# buck.net
KiCad netlist of a schematic drawn in Altium Designer
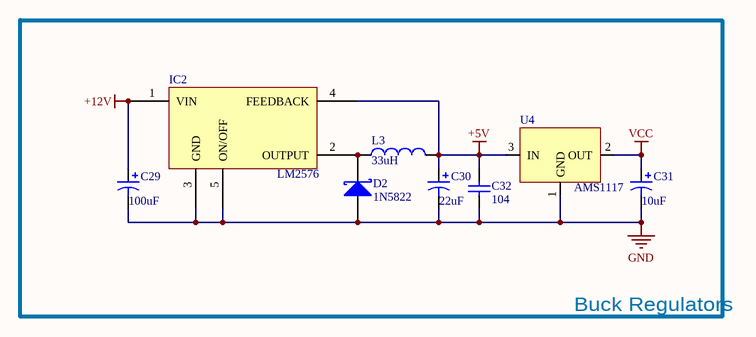
[diagram p0: buck.SchDoc]

(export (version "E")
  (design (tool "Eeschema 10.0.6"))
  (components
    (comp (ref "C29")
      (value "100uF")
      (footprint "CM E(8*10.2)")
      (description "Polarized Capacitor (Radial)")
      (fields (field (name "PUBLISHER") "Altium Limited"))
      (libsource (lib "Miscellaneous Devices") (part "Cap Pol1"))
    )
    (comp (ref "C30")
      (value "22uF")
      (footprint "CD A(3216)")
      (description "Polarized Capacitor (Radial)")
      (fields (field (name "PUBLISHER") "Altium Limited"))
      (libsource (lib "Miscellaneous Devices") (part "Cap Pol1"))
    )
    (comp (ref "C31")
      (value "10uF")
      (footprint "CD A(3216)")
      (description "Polarized Capacitor (Radial)")
      (fields (field (name "PUBLISHER") "Altium Limited"))
      (libsource (lib "Miscellaneous Devices") (part "Cap Pol1"))
    )
    (comp (ref "C32")
      (value "104")
      (footprint "C 0603_L")
      (description "Capacitor")
      (fields (field (name "PUBLISHER") "Altium Limited"))
      (libsource (lib "Miscellaneous Devices") (part "Cap"))
    )
    (comp (ref "D2")
      (value "1N5822")
      (footprint "SMC")
      (description "Schottky Rectifier")
      (fields (field (name "PUBLISHER") "Altium Limited"))
      (libsource (lib "Miscellaneous Devices") (part "Diode 11DQ03"))
    )
    (comp (ref "IC2")
      (value "LM2576")
      (footprint "TO263-5A")
      (description "稳压")
      (libsource (lib "Chip") (part "LM2576"))
    )
    (comp (ref "L3")
      (value "33uH")
      (footprint "CDRH127")
      (description "Inductor")
      (fields (field (name "PUBLISHER") "Altium Limited"))
      (libsource (lib "Miscellaneous Devices") (part "Inductor"))
    )
    (comp (ref "U4") (value "AMS1117") (footprint "SOT_223") (libsource (lib "主控板载芯片") (part "AMS1117")))
  )
  (nets
    (net (code "1") (name "+5V") (class "Default")
      (node (ref "C30") (pin "1") (pinfunction "1_1") (pintype "passive"))
      (node (ref "C32") (pin "2") (pinfunction "2_2") (pintype "passive"))
      (node (ref "IC2") (pin "4") (pinfunction "FEEDBACK_4") (pintype "passive"))
      (node (ref "L3") (pin "2") (pinfunction "2_2") (pintype "passive"))
      (node (ref "U4") (pin "3") (pinfunction "IN_3") (pintype "passive"))
    )
    (net (code "2") (name "+12V") (class "Default")
      (node (ref "C29") (pin "1") (pinfunction "1_1") (pintype "passive"))
      (node (ref "IC2") (pin "1") (pinfunction "VIN_1") (pintype "passive"))
    )
    (net (code "3") (name "GND") (class "Default")
      (node (ref "C29") (pin "2") (pinfunction "2_2") (pintype "passive"))
      (node (ref "C30") (pin "2") (pinfunction "2_2") (pintype "passive"))
      (node (ref "C31") (pin "2") (pinfunction "2_2") (pintype "passive"))
      (node (ref "C32") (pin "1") (pinfunction "1_1") (pintype "passive"))
      (node (ref "D2") (pin "1") (pinfunction "A_1") (pintype "passive"))
      (node (ref "IC2") (pin "3") (pinfunction "GND_3") (pintype "passive"))
      (node (ref "IC2") (pin "5") (pinfunction "ON/OFF_5") (pintype "passive"))
      (node (ref "U4") (pin "1") (pinfunction "GND_1") (pintype "passive"))
    )
    (net (code "4") (name "Net-(D2-K)") (class "Default")
      (node (ref "D2") (pin "2") (pinfunction "K_2") (pintype "passive"))
      (node (ref "IC2") (pin "2") (pinfunction "OUTPUT_2") (pintype "passive"))
      (node (ref "L3") (pin "1") (pinfunction "1_1") (pintype "passive"))
    )
    (net (code "5") (name "VCC") (class "Default")
      (node (ref "C31") (pin "1") (pinfunction "1_1") (pintype "passive"))
      (node (ref "U4") (pin "2") (pinfunction "OUT_2") (pintype "passive"))
    )
  )
)
